# 5v-3v3-converter.net
KiCad netlist of a schematic drawn in EAGLE
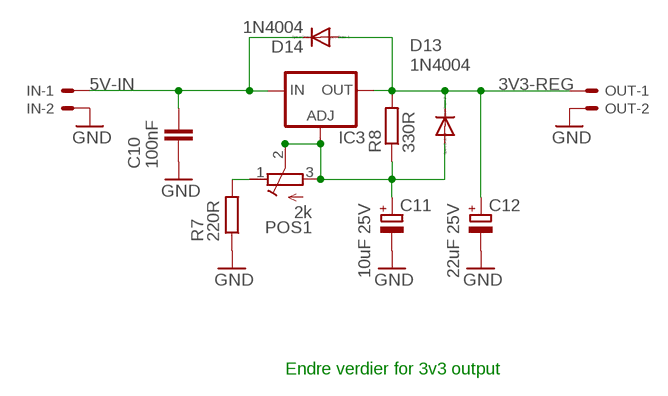
[diagram p0: schematic, sheet 1]

(export (version "E")
  (design (tool "Eeschema 10.0.6"))
  (components
    (comp (ref "C10")
      (value "100nF")
      (footprint "eagle-import:C050-025X075")
      (libsource (lib "eagle-import") (part "C-EU050-025X075"))
    )
    (comp (ref "C11")
      (value "10uF 25V")
      (footprint "eagle-import:E2,5-5")
      (libsource (lib "eagle-import") (part "CPOL-EUE2.5-5"))
    )
    (comp (ref "C12")
      (value "22uF 25V")
      (footprint "eagle-import:E2,5-5")
      (libsource (lib "eagle-import") (part "CPOL-EUE2.5-5"))
    )
    (comp (ref "D13")
      (value "1N4004")
      (footprint "eagle-import:DO41-10")
      (libsource (lib "eagle-import") (part "1N4004"))
    )
    (comp (ref "D14")
      (value "1N4004")
      (footprint "eagle-import:DO41-10")
      (libsource (lib "eagle-import") (part "1N4004"))
    )
    (comp (ref "IC3")
      (value "LM317TS")
      (footprint "eagle-import:317TS")
      (libsource (lib "eagle-import") (part "LM317TS"))
    )
    (comp (ref "IN")
      (value "KK-156-2")
      (footprint "eagle-import:KK-156-2")
      (libsource (lib "eagle-import") (part "KK-156-2"))
    )
    (comp (ref "OUT")
      (value "KK-156-2")
      (footprint "eagle-import:KK-156-2")
      (libsource (lib "eagle-import") (part "KK-156-2"))
    )
    (comp (ref "POS1")
      (value "2k")
      (footprint "eagle-import:RTRIMT93YA")
      (libsource (lib "eagle-import") (part "R-TRIMMT93YA"))
    )
    (comp (ref "R7")
      (value "220R")
      (footprint "eagle-import:0207_7")
      (libsource (lib "eagle-import") (part "R-EU_0207/7"))
    )
    (comp (ref "R8")
      (value "330R")
      (footprint "eagle-import:0207_7")
      (libsource (lib "eagle-import") (part "R-EU_0207/7"))
    )
  )
  (nets
    (net (code "1") (name "/3V3-REG") (class "Default")
      (node (ref "C12") (pin "+") (pinfunction "+_+") (pintype "passive"))
      (node (ref "D13") (pin "C") (pinfunction "C_C") (pintype "passive"))
      (node (ref "D14") (pin "A") (pinfunction "A_A") (pintype "passive"))
      (node (ref "IC3") (pin "2") (pinfunction "OUT_2") (pintype "passive"))
      (node (ref "OUT") (pin "1") (pinfunction "S_1") (pintype "passive"))
      (node (ref "R8") (pin "2") (pinfunction "2_2") (pintype "passive"))
    )
    (net (code "2") (name "/5V-IN") (class "Default")
      (node (ref "C10") (pin "1") (pinfunction "1_1") (pintype "passive"))
      (node (ref "D14") (pin "C") (pinfunction "C_C") (pintype "passive"))
      (node (ref "IC3") (pin "3") (pinfunction "IN_3") (pintype "input"))
      (node (ref "IN") (pin "1") (pinfunction "S_1") (pintype "passive"))
    )
    (net (code "3") (name "GND") (class "Default")
      (node (ref "C10") (pin "2") (pinfunction "2_2") (pintype "passive"))
      (node (ref "C11") (pin "-") (pinfunction "-_-") (pintype "passive"))
      (node (ref "C12") (pin "-") (pinfunction "-_-") (pintype "passive"))
      (node (ref "IN") (pin "2") (pinfunction "S_2") (pintype "passive"))
      (node (ref "OUT") (pin "2") (pinfunction "S_2") (pintype "passive"))
      (node (ref "R7") (pin "1") (pinfunction "1_1") (pintype "passive"))
    )
    (net (code "4") (name "Net-(IC3-ADJ)") (class "Default")
      (node (ref "C11") (pin "+") (pinfunction "+_+") (pintype "passive"))
      (node (ref "D13") (pin "A") (pinfunction "A_A") (pintype "passive"))
      (node (ref "IC3") (pin "1") (pinfunction "ADJ_1") (pintype "input"))
      (node (ref "POS1") (pin "2") (pinfunction "S_2") (pintype "passive"))
      (node (ref "POS1") (pin "3") (pinfunction "A_3") (pintype "passive"))
      (node (ref "R8") (pin "1") (pinfunction "1_1") (pintype "passive"))
    )
    (net (code "5") (name "Net-(POS1-E)") (class "Default")
      (node (ref "POS1") (pin "1") (pinfunction "E_1") (pintype "passive"))
      (node (ref "R7") (pin "2") (pinfunction "2_2") (pintype "passive"))
    )
  )
)
